# EEPROM.net
KiCad netlist of a schematic drawn in Altium Designer
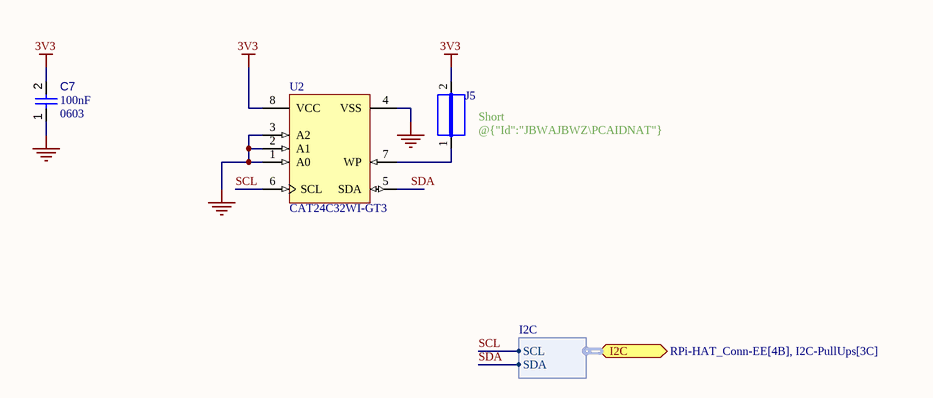
[diagram p0: EEPROM.SchDoc]

(export (version "E")
  (design (tool "Eeschema 10.0.6"))
  (components
    (comp (ref "C7")
      (value "100nF")
      (footprint "CAPC1608X90X40NL10T20")
      (description "Chip Capacitor, 100 nF, +/- 10%, 50 V, 0603 (1608 Metric)")
      (fields
        (field (name "TOLERANCE") "10%")
        (field (name "CASE/PACKAGE") "0603")
        (field (name "Comment") "Capacitor 100 nF +/-10% 50 V 0603")
      )
      (libsource (lib "Twill Technology Inc") (part "CAP-NP-2"))
    )
    (comp (ref "J5")
      (value "JUMPER")
      (footprint "JUMPER")
      (libsource (lib "Twill Technology Inc") (part "JUMPER"))
    )
    (comp (ref "U2")
      (value "CAT24C32WI-GT3")
      (footprint "ONSC-SOIC-8-751BD-01_M")
      (fields (field (name "MANUFACTURER") "ON Semiconductor"))
      (libsource (lib "Twill Technology Inc") (part "ONSC-CAT24C32-SOIC-8"))
    )
  )
  (nets
    (net (code "2") (name "/SCL") (class "Default")
      (node (ref "U2") (pin "6") (pinfunction "SCL_6") (pintype "input"))
    )
    (net (code "3") (name "/SDA") (class "Default")
      (node (ref "U2") (pin "5") (pinfunction "SDA_5") (pintype "bidirectional"))
    )
    (net (code "5") (name "3V3") (class "Default")
      (node (ref "C7") (pin "2") (pinfunction "2_2") (pintype "passive"))
      (node (ref "J5") (pin "2") (pinfunction "2_2") (pintype "passive"))
      (node (ref "U2") (pin "8") (pinfunction "VCC_8") (pintype "power_in"))
    )
    (net (code "6") (name "GND") (class "Default")
      (node (ref "C7") (pin "1") (pinfunction "1_1") (pintype "passive"))
      (node (ref "U2") (pin "1") (pinfunction "A0_1") (pintype "input"))
      (node (ref "U2") (pin "2") (pinfunction "A1_2") (pintype "input"))
      (node (ref "U2") (pin "3") (pinfunction "A2_3") (pintype "input"))
      (node (ref "U2") (pin "4") (pinfunction "VSS_4") (pintype "power_in"))
    )
    (net (code "7") (name "Net-(U2-WP)") (class "Default")
      (node (ref "J5") (pin "1") (pinfunction "1_1") (pintype "passive"))
      (node (ref "U2") (pin "7") (pinfunction "WP_7") (pintype "input"))
    )
  )
)
